# 3_pure60-mcu.net
KiCad netlist of a schematic drawn in Altium Designer
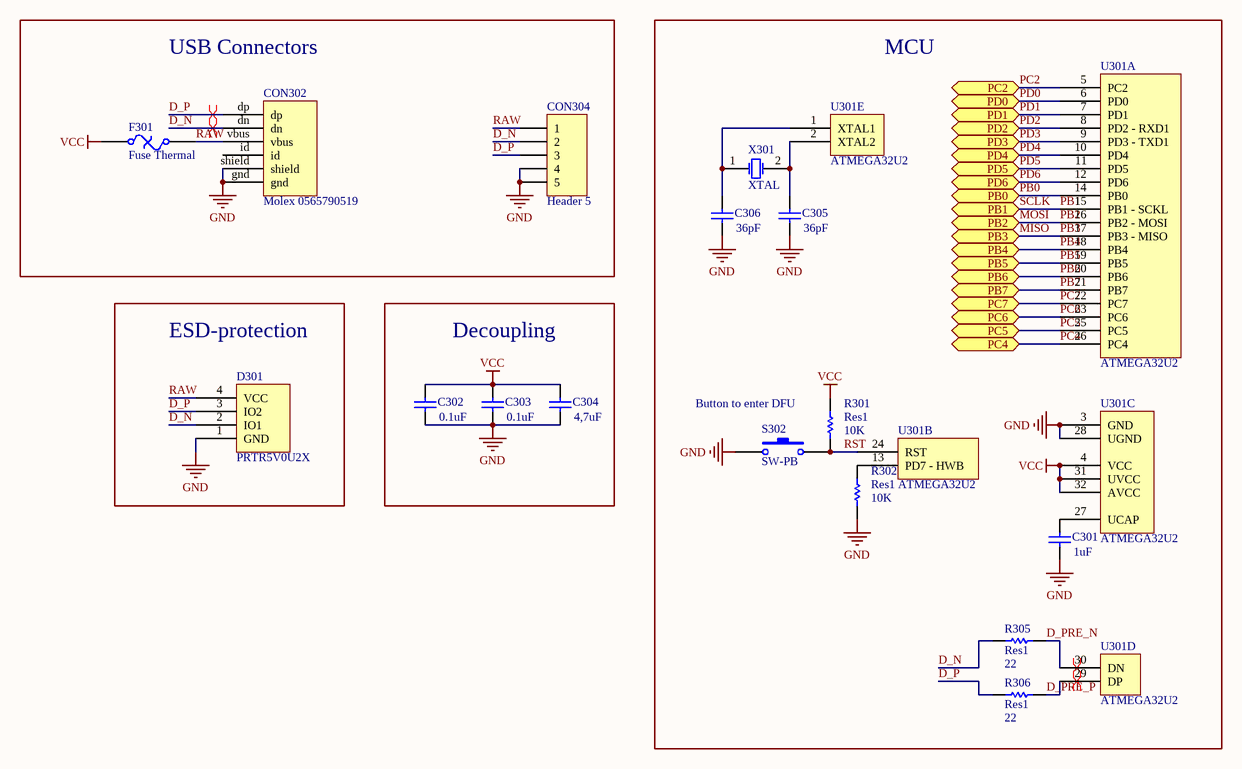
[diagram p0: 3_pure60-mcu.SchDoc]

(export (version "E")
  (design (tool "Eeschema 10.0.6"))
  (components
    (comp (ref "C301")
      (value "1uF")
      (footprint "C0603[1608]")
      (description "Capacitor")
      (fields (field (name "MFG") "KEMET") (field (name "MRF.PART") "CL10A105KB8NNNC"))
      (libsource (lib "Miscellaneous Devices") (part "Cap"))
    )
    (comp (ref "C302")
      (value "0.1uF")
      (footprint "C0603[1608]")
      (description "Capacitor")
      (fields (field (name "MFG") "KEMET") (field (name "MRF.PART") "CC0603KRX7R9BB104"))
      (libsource (lib "Miscellaneous Devices") (part "Cap"))
    )
    (comp (ref "C303")
      (value "0.1uF")
      (footprint "C0603[1608]")
      (description "Capacitor")
      (fields (field (name "MFG") "KEMET") (field (name "MRF.PART") "CC0603KRX7R9BB104"))
      (libsource (lib "Miscellaneous Devices") (part "Cap"))
    )
    (comp (ref "C304")
      (value "4,7uF")
      (footprint "C1206[3216]")
      (description "Capacitor")
      (fields (field (name "MFG") "KEMET") (field (name "MRF.PART") "1206B475K500NT"))
      (libsource (lib "Miscellaneous Devices") (part "Cap"))
    )
    (comp (ref "C305")
      (value "36pF")
      (footprint "C0603[1608]")
      (description "Capacitor")
      (fields (field (name "MFG") "KEMET") (field (name "MRF.PART") "CL10C360JB8NNNC"))
      (libsource (lib "Miscellaneous Devices") (part "Cap"))
    )
    (comp (ref "C306")
      (value "36pF")
      (footprint "C0603[1608]")
      (description "Capacitor")
      (fields (field (name "MFG") "KEMET") (field (name "MRF.PART") "CL10C360JB8NNNC"))
      (libsource (lib "Miscellaneous Devices") (part "Cap"))
    )
    (comp (ref "CON302")
      (value "Molex 0565790519")
      (footprint "Molex 0565790519")
      (libsource (lib "Keebs") (part "Molex 0565790519"))
    )
    (comp (ref "CON304")
      (value "Header 5")
      (footprint "JST SM04B-SRSS-TB")
      (description "JST for USB daughter board")
      (fields (field (name "MFG") "JST Sales America Inc.") (field (name "MRF.PART") "SM04B-SRSS-TB(LF)(SN)"))
      (libsource (lib "Miscellaneous Connectors") (part "Header 5"))
    )
    (comp (ref "D301")
      (value "PRTR5V0U2X")
      (footprint "SOT190P237X120-4N")
      (fields (field (name "MFG") "Nexperia USA Inc.") (field (name "MRF.PART") "UET14A05L03"))
      (libsource (lib "Schlib1") (part "PRTR5V0U2X"))
    )
    (comp (ref "F301")
      (value "Fuse Thermal")
      (footprint "C1206[3216]")
      (description "Thermal Fuse")
      (fields (field (name "MFG") "Bel Fuse Inc.") (field (name "MRF.PART") "ASMD1206-050"))
      (libsource (lib "Miscellaneous Devices") (part "Fuse Thermal"))
    )
    (comp (ref "R301")
      (value "Res1")
      (footprint "R0603[1608]")
      (description "Resistor")
      (fields
        (field (name "ALTIUM_VALUE") "10K")
        (field (name "MFG") "Panasonic Electronic Components")
        (field (name "MRF.PART") "0603WAF1002T5E")
      )
      (libsource (lib "Miscellaneous Devices") (part "Res1"))
    )
    (comp (ref "R302")
      (value "Res1")
      (footprint "R0603[1608]")
      (description "Resistor")
      (fields
        (field (name "ALTIUM_VALUE") "10K")
        (field (name "MFG") "Panasonic Electronic Components")
        (field (name "MRF.PART") "0603WAF1002T5E")
      )
      (libsource (lib "Miscellaneous Devices") (part "Res1"))
    )
    (comp (ref "R305")
      (value "Res1")
      (footprint "R0603[1608]")
      (description "Resistor")
      (fields
        (field (name "ALTIUM_VALUE") "22")
        (field (name "MFG") "Panasonic Electronic Components")
        (field (name "MRF.PART") "0603WAF220JT5E")
      )
      (libsource (lib "Miscellaneous Devices") (part "Res1"))
    )
    (comp (ref "R306")
      (value "Res1")
      (footprint "R0603[1608]")
      (description "Resistor")
      (fields
        (field (name "ALTIUM_VALUE") "22")
        (field (name "MFG") "Panasonic Electronic Components")
        (field (name "MRF.PART") "0603WAF220JT5E")
      )
      (libsource (lib "Miscellaneous Devices") (part "Res1"))
    )
    (comp (ref "S302")
      (value "SW-PB")
      (footprint "Combo switch")
      (description "Switch")
      (fields (field (name "MFG") "C&K") (field (name "MRF.PART") "TS-1187A-C-D-B"))
      (libsource (lib "Miscellaneous Devices") (part "SW-PB"))
    )
    (comp (ref "U301")
      (value "ATMEGA32U2")
      (footprint "ATMEGA32U2-QFN")
      (fields (field (name "MFG") "Microchip Technology") (field (name "MRF.PART") "ATMEGA32U2-MU"))
      (libsource (lib "") (part "ATMEGA32U2_1"))
    )
    (comp (ref "X301")
      (value "XTAL")
      (footprint "CTS 445-series crystal")
      (description "Crystal Oscillator")
      (fields (field (name "MRF.PART") "X503216MSB2GI"))
      (libsource (lib "Miscellaneous Devices") (part "XTAL"))
    )
  )
  (nets
    (net (code "1") (name "/D_N") (class "Default")
      (node (ref "CON302") (pin "dn") (pinfunction "dn_dn") (pintype "passive"))
      (node (ref "CON304") (pin "2") (pinfunction "2_2") (pintype "passive"))
      (node (ref "D301") (pin "2") (pinfunction "IO1_2") (pintype "passive"))
      (node (ref "R305") (pin "2") (pinfunction "2_2") (pintype "passive"))
    )
    (net (code "2") (name "/D_P") (class "Default")
      (node (ref "CON302") (pin "dp") (pinfunction "dp_dp") (pintype "passive"))
      (node (ref "CON304") (pin "3") (pinfunction "3_3") (pintype "passive"))
      (node (ref "D301") (pin "3") (pinfunction "IO2_3") (pintype "passive"))
      (node (ref "R306") (pin "2") (pinfunction "2_2") (pintype "passive"))
    )
    (net (code "3") (name "/D_PRE_N") (class "Default")
      (node (ref "R305") (pin "1") (pinfunction "1_1") (pintype "passive"))
      (node (ref "U301") (pin "30") (pinfunction "DN_30") (pintype "passive"))
    )
    (net (code "4") (name "/D_PRE_P") (class "Default")
      (node (ref "R306") (pin "1") (pinfunction "1_1") (pintype "passive"))
      (node (ref "U301") (pin "29") (pinfunction "DP_29") (pintype "passive"))
    )
    (net (code "5") (name "/MISO") (class "Default")
      (node (ref "U301") (pin "17") (pinfunction "PB3_-_MISO_17") (pintype "passive"))
    )
    (net (code "6") (name "/MOSI") (class "Default")
      (node (ref "U301") (pin "16") (pinfunction "PB2_-_MOSI_16") (pintype "passive"))
    )
    (net (code "7") (name "/PB0") (class "Default")
      (node (ref "U301") (pin "14") (pinfunction "PB0_14") (pintype "passive"))
    )
    (net (code "8") (name "/PB1") (class "Default")
      (node (ref "U301") (pin "15") (pinfunction "PB1_-_SCKL_15") (pintype "passive"))
    )
    (net (code "9") (name "/PB4") (class "Default")
      (node (ref "U301") (pin "18") (pinfunction "PB4_18") (pintype "passive"))
    )
    (net (code "10") (name "/PB5") (class "Default")
      (node (ref "U301") (pin "19") (pinfunction "PB5_19") (pintype "passive"))
    )
    (net (code "11") (name "/PB6") (class "Default")
      (node (ref "U301") (pin "20") (pinfunction "PB6_20") (pintype "passive"))
    )
    (net (code "12") (name "/PB7") (class "Default")
      (node (ref "U301") (pin "21") (pinfunction "PB7_21") (pintype "passive"))
    )
    (net (code "13") (name "/PC2") (class "Default")
      (node (ref "U301") (pin "5") (pinfunction "PC2_5") (pintype "passive"))
    )
    (net (code "14") (name "/PC4") (class "Default")
      (node (ref "U301") (pin "26") (pinfunction "PC4_26") (pintype "passive"))
    )
    (net (code "15") (name "/PC5") (class "Default")
      (node (ref "U301") (pin "25") (pinfunction "PC5_25") (pintype "passive"))
    )
    (net (code "16") (name "/PC6") (class "Default")
      (node (ref "U301") (pin "23") (pinfunction "PC6_23") (pintype "passive"))
    )
    (net (code "17") (name "/PC7") (class "Default")
      (node (ref "U301") (pin "22") (pinfunction "PC7_22") (pintype "passive"))
    )
    (net (code "18") (name "/PD0") (class "Default")
      (node (ref "U301") (pin "6") (pinfunction "PD0_6") (pintype "passive"))
    )
    (net (code "19") (name "/PD1") (class "Default")
      (node (ref "U301") (pin "7") (pinfunction "PD1_7") (pintype "passive"))
    )
    (net (code "20") (name "/PD2") (class "Default")
      (node (ref "U301") (pin "8") (pinfunction "PD2_-_RXD1_8") (pintype "passive"))
    )
    (net (code "21") (name "/PD3") (class "Default")
      (node (ref "U301") (pin "9") (pinfunction "PD3_-_TXD1_9") (pintype "passive"))
    )
    (net (code "22") (name "/PD4") (class "Default")
      (node (ref "U301") (pin "10") (pinfunction "PD4_10") (pintype "passive"))
    )
    (net (code "23") (name "/PD5") (class "Default")
      (node (ref "U301") (pin "11") (pinfunction "PD5_11") (pintype "passive"))
    )
    (net (code "24") (name "/PD6") (class "Default")
      (node (ref "U301") (pin "12") (pinfunction "PD6_12") (pintype "passive"))
    )
    (net (code "25") (name "/RAW") (class "Default")
      (node (ref "CON302") (pin "vbus") (pinfunction "vbus_vbus") (pintype "passive"))
      (node (ref "CON304") (pin "1") (pinfunction "1_1") (pintype "passive"))
      (node (ref "D301") (pin "4") (pinfunction "VCC_4") (pintype "passive"))
      (node (ref "F301") (pin "2") (pinfunction "2_2") (pintype "passive"))
    )
    (net (code "26") (name "/RST") (class "Default")
      (node (ref "R301") (pin "2") (pinfunction "2_2") (pintype "passive"))
      (node (ref "S302") (pin "2") (pinfunction "2_2") (pintype "passive"))
      (node (ref "U301") (pin "24") (pinfunction "RST_24") (pintype "passive"))
    )
    (net (code "27") (name "GND") (class "Default")
      (node (ref "C301") (pin "1") (pinfunction "1_1") (pintype "passive"))
      (node (ref "C302") (pin "1") (pinfunction "1_1") (pintype "passive"))
      (node (ref "C303") (pin "1") (pinfunction "1_1") (pintype "passive"))
      (node (ref "C304") (pin "1") (pinfunction "1_1") (pintype "passive"))
      (node (ref "C305") (pin "1") (pinfunction "1_1") (pintype "passive"))
      (node (ref "C306") (pin "1") (pinfunction "1_1") (pintype "passive"))
      (node (ref "CON302") (pin "gnd") (pinfunction "gnd_gnd") (pintype "passive"))
      (node (ref "CON302") (pin "shield") (pinfunction "shield_shield") (pintype "passive"))
      (node (ref "CON304") (pin "4") (pinfunction "4_4") (pintype "passive"))
      (node (ref "CON304") (pin "5") (pinfunction "5_5") (pintype "passive"))
      (node (ref "D301") (pin "1") (pinfunction "GND_1") (pintype "passive"))
      (node (ref "R302") (pin "2") (pinfunction "2_2") (pintype "passive"))
      (node (ref "S302") (pin "1") (pinfunction "1_1") (pintype "passive"))
      (node (ref "U301") (pin "28") (pinfunction "UGND_28") (pintype "passive"))
      (node (ref "U301") (pin "3") (pinfunction "GND_3") (pintype "passive"))
    )
    (net (code "28") (name "Net-(U301B-PD7_-_HWB)") (class "Default")
      (node (ref "R302") (pin "1") (pinfunction "1_1") (pintype "passive"))
      (node (ref "U301") (pin "13") (pinfunction "PD7_-_HWB_13") (pintype "passive"))
    )
    (net (code "29") (name "Net-(U301C-UCAP)") (class "Default")
      (node (ref "C301") (pin "2") (pinfunction "2_2") (pintype "passive"))
      (node (ref "U301") (pin "27") (pinfunction "UCAP_27") (pintype "passive"))
    )
    (net (code "30") (name "Net-(U301E-XTAL1)") (class "Default")
      (node (ref "C306") (pin "2") (pinfunction "2_2") (pintype "passive"))
      (node (ref "U301") (pin "1") (pinfunction "XTAL1_1") (pintype "passive"))
      (node (ref "X301") (pin "1") (pinfunction "OSC1_1") (pintype "passive"))
    )
    (net (code "31") (name "Net-(U301E-XTAL2)") (class "Default")
      (node (ref "C305") (pin "2") (pinfunction "2_2") (pintype "passive"))
      (node (ref "U301") (pin "2") (pinfunction "XTAL2_2") (pintype "passive"))
      (node (ref "X301") (pin "2") (pinfunction "OSC2_2") (pintype "passive"))
    )
    (net (code "32") (name "VCC") (class "Default")
      (node (ref "C302") (pin "2") (pinfunction "2_2") (pintype "passive"))
      (node (ref "C303") (pin "2") (pinfunction "2_2") (pintype "passive"))
      (node (ref "C304") (pin "2") (pinfunction "2_2") (pintype "passive"))
      (node (ref "F301") (pin "1") (pinfunction "1_1") (pintype "passive"))
      (node (ref "R301") (pin "1") (pinfunction "1_1") (pintype "passive"))
      (node (ref "U301") (pin "31") (pinfunction "UVCC_31") (pintype "passive"))
      (node (ref "U301") (pin "32") (pinfunction "AVCC_32") (pintype "passive"))
      (node (ref "U301") (pin "4") (pinfunction "VCC_4") (pintype "passive"))
    )
    (net (code "33") (name "unconnected-(CON302-Padid)") (class "Default")
      (node (ref "CON302") (pin "id") (pinfunction "id_id") (pintype "passive"))
    )
  )
)
